# 2016_FDP_STRATEGIE.net
KiCad netlist of a schematic drawn in Altium Designer
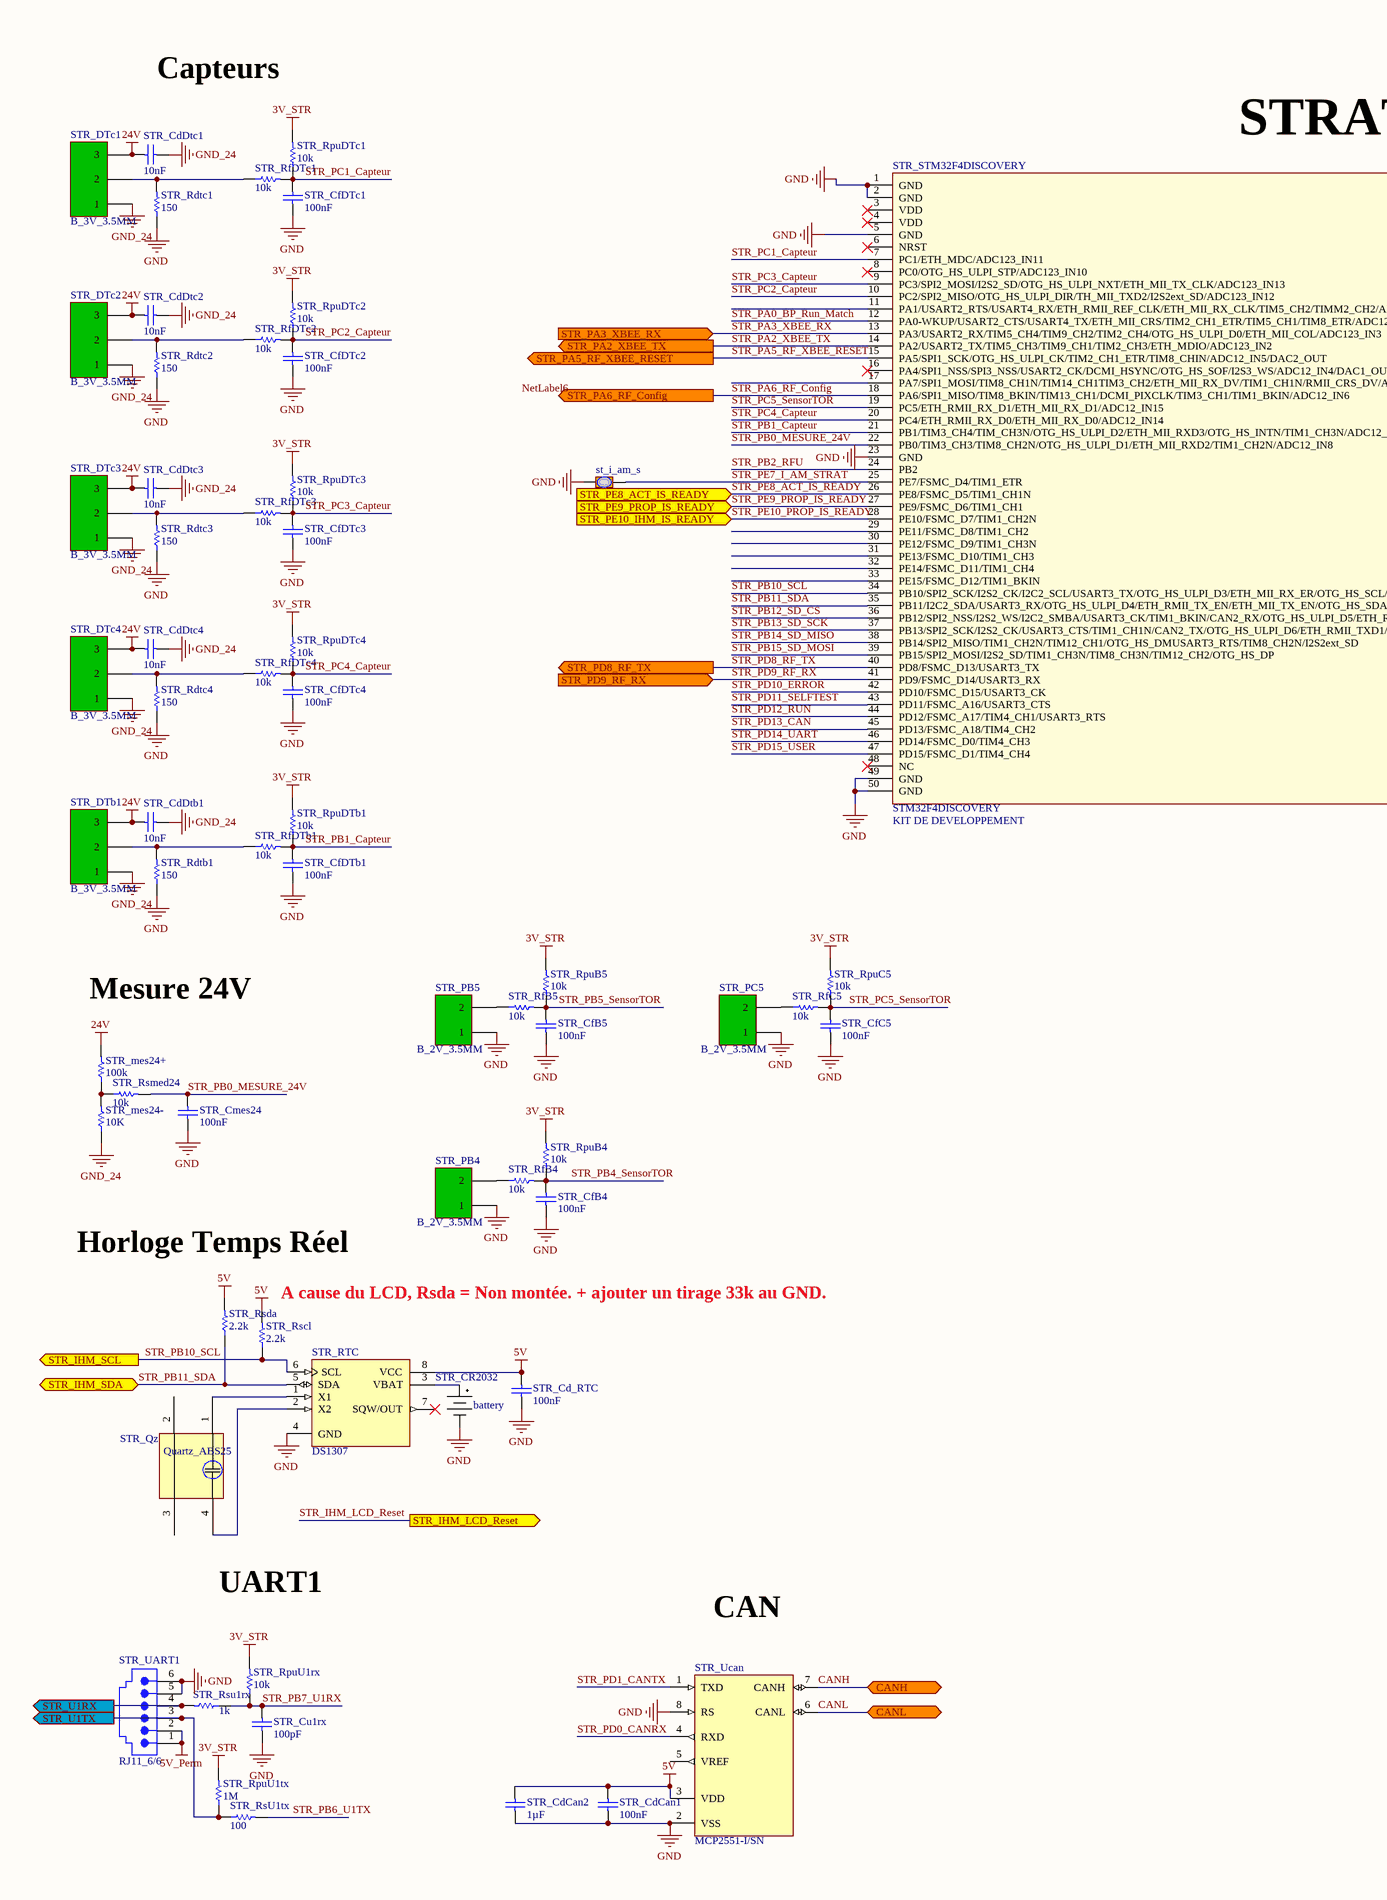
[diagram p0: 2016_FDP_STRATEGIE.SchDoc, left]
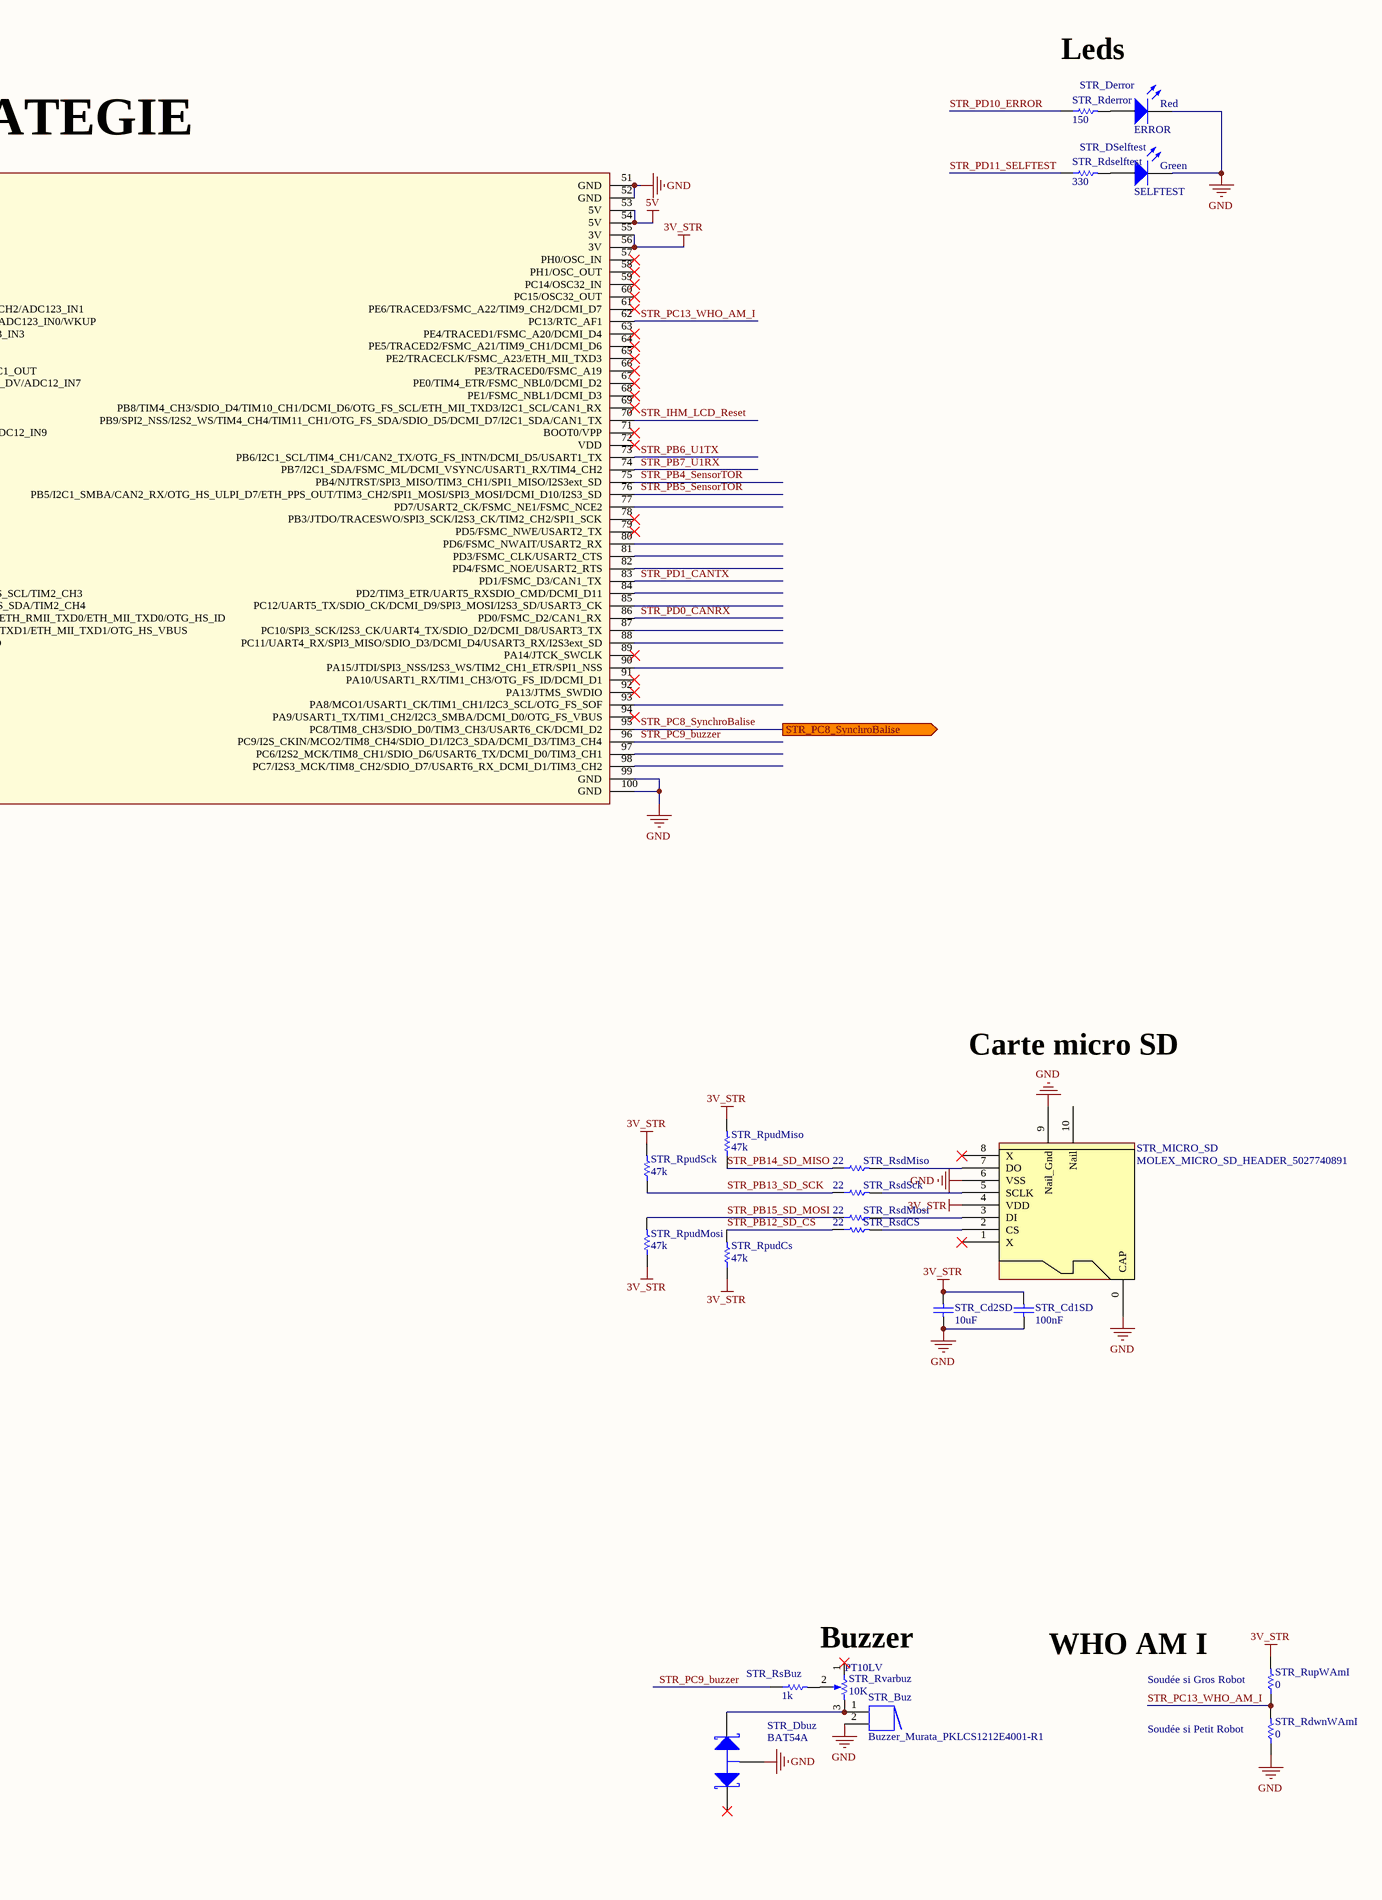
[diagram p1: 2016_FDP_STRATEGIE.SchDoc, right]

(export (version "E")
  (design (tool "Eeschema 10.0.6"))
  (components
    (comp (ref "STR_Buz")
      (value "Buzzer_Murata_PKLCS1212E4001-R1")
      (footprint "Buzzer_Murata PKLCS1212")
      (fields
        (field (name "MANUFACTURER") "MURATA")
        (field (name "MANUFACTURER PART NUMBER") "PKLCS1212E4001-R1")
      )
      (libsource (lib "DG_Buzzer") (part "Buzzer_Murata_PKLCS1212E4001-R1"))
    )
    (comp (ref "STR_Cd1SD")
      (value "100nF")
      (footprint "C0805_N")
      (description "Capacitor")
      (fields (field (name "PUBLISHER") "Altium Limited"))
      (libsource (lib "_ROBOT") (part "Condensateur"))
    )
    (comp (ref "STR_Cd2SD")
      (value "10uF")
      (footprint "C1206_N")
      (description "Capacitor")
      (fields (field (name "PUBLISHER") "Altium Limited"))
      (libsource (lib "_ROBOT") (part "Condensateur"))
    )
    (comp (ref "STR_CdCan1")
      (value "100nF")
      (footprint "C0805_N")
      (description "Capacitor")
      (fields (field (name "PUBLISHER") "Altium Limited"))
      (libsource (lib "_ROBOT") (part "Condensateur"))
    )
    (comp (ref "STR_CdCan2")
      (value "1µF")
      (footprint "C0805_N")
      (description "Capacitor")
      (fields (field (name "PUBLISHER") "Altium Limited"))
      (libsource (lib "_ROBOT") (part "Condensateur"))
    )
    (comp (ref "STR_CdDtb1")
      (value "10nF")
      (footprint "C0805_N")
      (description "Capacitor")
      (fields (field (name "PUBLISHER") "Altium Limited"))
      (libsource (lib "_ROBOT") (part "Condensateur"))
    )
    (comp (ref "STR_CdDtc1")
      (value "10nF")
      (footprint "C0805_N")
      (description "Capacitor")
      (fields (field (name "PUBLISHER") "Altium Limited"))
      (libsource (lib "_ROBOT") (part "Condensateur"))
    )
    (comp (ref "STR_CdDtc2")
      (value "10nF")
      (footprint "C0805_N")
      (description "Capacitor")
      (fields (field (name "PUBLISHER") "Altium Limited"))
      (libsource (lib "_ROBOT") (part "Condensateur"))
    )
    (comp (ref "STR_CdDtc3")
      (value "10nF")
      (footprint "C0805_N")
      (description "Capacitor")
      (fields (field (name "PUBLISHER") "Altium Limited"))
      (libsource (lib "_ROBOT") (part "Condensateur"))
    )
    (comp (ref "STR_CdDtc4")
      (value "10nF")
      (footprint "C0805_N")
      (description "Capacitor")
      (fields (field (name "PUBLISHER") "Altium Limited"))
      (libsource (lib "_ROBOT") (part "Condensateur"))
    )
    (comp (ref "STR_Cd_RTC")
      (value "100nF")
      (footprint "C0805_N")
      (description "Capacitor")
      (fields (field (name "PUBLISHER") "Altium Limited"))
      (libsource (lib "_ROBOT") (part "Condensateur"))
    )
    (comp (ref "STR_CfB4")
      (value "100nF")
      (footprint "C0805_N")
      (description "Capacitor")
      (fields (field (name "PUBLISHER") "Altium Limited"))
      (libsource (lib "_ROBOT") (part "Condensateur"))
    )
    (comp (ref "STR_CfB5")
      (value "100nF")
      (footprint "C0805_N")
      (description "Capacitor")
      (fields (field (name "PUBLISHER") "Altium Limited"))
      (libsource (lib "_ROBOT") (part "Condensateur"))
    )
    (comp (ref "STR_CfC5")
      (value "100nF")
      (footprint "C0805_N")
      (description "Capacitor")
      (fields (field (name "PUBLISHER") "Altium Limited"))
      (libsource (lib "_ROBOT") (part "Condensateur"))
    )
    (comp (ref "STR_CfDTb1")
      (value "100nF")
      (footprint "C0805_N")
      (description "Capacitor")
      (fields (field (name "PUBLISHER") "Altium Limited"))
      (libsource (lib "_ROBOT") (part "Condensateur"))
    )
    (comp (ref "STR_CfDTc1")
      (value "100nF")
      (footprint "C0805_N")
      (description "Capacitor")
      (fields (field (name "PUBLISHER") "Altium Limited"))
      (libsource (lib "_ROBOT") (part "Condensateur"))
    )
    (comp (ref "STR_CfDTc2")
      (value "100nF")
      (footprint "C0805_N")
      (description "Capacitor")
      (fields (field (name "PUBLISHER") "Altium Limited"))
      (libsource (lib "_ROBOT") (part "Condensateur"))
    )
    (comp (ref "STR_CfDTc3")
      (value "100nF")
      (footprint "C0805_N")
      (description "Capacitor")
      (fields (field (name "PUBLISHER") "Altium Limited"))
      (libsource (lib "_ROBOT") (part "Condensateur"))
    )
    (comp (ref "STR_CfDTc4")
      (value "100nF")
      (footprint "C0805_N")
      (description "Capacitor")
      (fields (field (name "PUBLISHER") "Altium Limited"))
      (libsource (lib "_ROBOT") (part "Condensateur"))
    )
    (comp (ref "STR_Cmes24")
      (value "100nF")
      (footprint "C0805_N")
      (description "Capacitor")
      (fields (field (name "PUBLISHER") "Altium Limited"))
      (libsource (lib "_ROBOT") (part "Condensateur"))
    )
    (comp (ref "STR_CR2032")
      (value "battery")
      (footprint "Pile_boutton")
      (description "Battery, Pile")
      (fields (field (name "PUBLISHER") "Jean-Philippe Oudet"))
      (libsource (lib "LibPocketTag") (part "battery"))
    )
    (comp (ref "STR_Cu1rx")
      (value "100pF")
      (footprint "C0805_N")
      (description "Capacitor")
      (fields (field (name "PUBLISHER") "Altium Limited"))
      (libsource (lib "_ROBOT") (part "Condensateur"))
    )
    (comp (ref "STR_Dbuz")
      (value "BAT54A")
      (footprint "SOT23-3N")
      (description "DIODE SCHOTTKY DOUBLE")
      (fields (field (name "MANUFACTURER") "ZETEX"))
      (libsource (lib "_ROBOT") (part "Diode Shottky double  BAT54A"))
    )
    (comp (ref "STR_Derror")
      (value "ERROR")
      (footprint "LED_0805")
      (description "Typical LED")
      (fields (field (name "PUBLISHER") "Altium Limited"))
      (libsource (lib "_ROBOT") (part "LED"))
    )
    (comp (ref "STR_DSelftest")
      (value "SELFTEST")
      (footprint "LED_0805")
      (description "Typical LED")
      (fields (field (name "PUBLISHER") "Altium Limited"))
      (libsource (lib "_ROBOT") (part "LED"))
    )
    (comp (ref "STR_DTb1")
      (value "B_3V_3.5MM")
      (footprint "BORNIER_3V_3.5MM")
      (libsource (lib "Connecteur") (part "BORNIER_3V_3.5MM"))
    )
    (comp (ref "STR_DTc1")
      (value "B_3V_3.5MM")
      (footprint "BORNIER_3V_3.5MM")
      (libsource (lib "Connecteur") (part "BORNIER_3V_3.5MM"))
    )
    (comp (ref "STR_DTc2")
      (value "B_3V_3.5MM")
      (footprint "BORNIER_3V_3.5MM")
      (libsource (lib "Connecteur") (part "BORNIER_3V_3.5MM"))
    )
    (comp (ref "STR_DTc3")
      (value "B_3V_3.5MM")
      (footprint "BORNIER_3V_3.5MM")
      (libsource (lib "Connecteur") (part "BORNIER_3V_3.5MM"))
    )
    (comp (ref "STR_DTc4")
      (value "B_3V_3.5MM")
      (footprint "BORNIER_3V_3.5MM")
      (libsource (lib "Connecteur") (part "BORNIER_3V_3.5MM"))
    )
    (comp (ref "STR_mes24+")
      (value "100k")
      (footprint "R1206_N")
      (description "Resistor")
      (fields (field (name "PUBLISHER") "Altium Limited"))
      (libsource (lib "_ROBOT") (part "Resistor"))
    )
    (comp (ref "STR_mes24-")
      (value "10K")
      (footprint "R1206_N")
      (description "Resistor")
      (fields (field (name "PUBLISHER") "Altium Limited"))
      (libsource (lib "_ROBOT") (part "Resistor"))
    )
    (comp (ref "STR_MICRO_SD")
      (value "MOLEX_MICRO_SD_HEADER_5027740891")
      (footprint "MOLEX_MICRO_SD_HEADER_5027740891")
      (libsource (lib "Connecteur") (part "MOLEX_MICRO_SD_HEADER_5027740891"))
    )
    (comp (ref "STR_PB4")
      (value "B_2V_3.5MM")
      (footprint "BORNIER_2V_3.5MM")
      (libsource (lib "Connecteur") (part "BORNIER_2V_3.5MM"))
    )
    (comp (ref "STR_PB5")
      (value "B_2V_3.5MM")
      (footprint "BORNIER_2V_3.5MM")
      (libsource (lib "Connecteur") (part "BORNIER_2V_3.5MM"))
    )
    (comp (ref "STR_PC5")
      (value "B_2V_3.5MM")
      (footprint "BORNIER_2V_3.5MM")
      (libsource (lib "Connecteur") (part "BORNIER_2V_3.5MM"))
    )
    (comp (ref "STR_Qz")
      (value "Quartz_ABS25")
      (footprint "Quartz_ABS25")
      (libsource (lib "_ROBOT") (part "Quartz_ABS25"))
    )
    (comp (ref "STR_Rderror")
      (value "150")
      (footprint "R1206_N")
      (description "Resistor")
      (fields (field (name "PUBLISHER") "Altium Limited"))
      (libsource (lib "_ROBOT") (part "Resistor"))
    )
    (comp (ref "STR_Rdselftest")
      (value "330")
      (footprint "R1206_N")
      (description "Resistor")
      (fields (field (name "PUBLISHER") "Altium Limited"))
      (libsource (lib "_ROBOT") (part "Resistor"))
    )
    (comp (ref "STR_Rdtb1")
      (value "150")
      (footprint "R1206_N")
      (description "Resistor")
      (fields (field (name "PUBLISHER") "Altium Limited"))
      (libsource (lib "_ROBOT") (part "Resistor"))
    )
    (comp (ref "STR_Rdtc1")
      (value "150")
      (footprint "R1206_N")
      (description "Resistor")
      (fields (field (name "PUBLISHER") "Altium Limited"))
      (libsource (lib "_ROBOT") (part "Resistor"))
    )
    (comp (ref "STR_Rdtc2")
      (value "150")
      (footprint "R1206_N")
      (description "Resistor")
      (fields (field (name "PUBLISHER") "Altium Limited"))
      (libsource (lib "_ROBOT") (part "Resistor"))
    )
    (comp (ref "STR_Rdtc3")
      (value "150")
      (footprint "R1206_N")
      (description "Resistor")
      (fields (field (name "PUBLISHER") "Altium Limited"))
      (libsource (lib "_ROBOT") (part "Resistor"))
    )
    (comp (ref "STR_Rdtc4")
      (value "150")
      (footprint "R1206_N")
      (description "Resistor")
      (fields (field (name "PUBLISHER") "Altium Limited"))
      (libsource (lib "_ROBOT") (part "Resistor"))
    )
    (comp (ref "STR_RdwnWAmI")
      (value "0")
      (footprint "R1206_N")
      (description "Resistor")
      (fields (field (name "PUBLISHER") "Altium Limited"))
      (libsource (lib "_ROBOT") (part "Resistor"))
    )
    (comp (ref "STR_RfB4")
      (value "10k")
      (footprint "R1206_N")
      (description "Resistor")
      (fields (field (name "PUBLISHER") "Altium Limited"))
      (libsource (lib "_ROBOT") (part "Resistor"))
    )
    (comp (ref "STR_RfB5")
      (value "10k")
      (footprint "R1206_N")
      (description "Resistor")
      (fields (field (name "PUBLISHER") "Altium Limited"))
      (libsource (lib "_ROBOT") (part "Resistor"))
    )
    (comp (ref "STR_RfC5")
      (value "10k")
      (footprint "R1206_N")
      (description "Resistor")
      (fields (field (name "PUBLISHER") "Altium Limited"))
      (libsource (lib "_ROBOT") (part "Resistor"))
    )
    (comp (ref "STR_RfDTb1")
      (value "10k")
      (footprint "R1206_N")
      (description "Resistor")
      (fields (field (name "PUBLISHER") "Altium Limited"))
      (libsource (lib "_ROBOT") (part "Resistor"))
    )
    (comp (ref "STR_RfDTc1")
      (value "10k")
      (footprint "R1206_N")
      (description "Resistor")
      (fields (field (name "PUBLISHER") "Altium Limited"))
      (libsource (lib "_ROBOT") (part "Resistor"))
    )
    (comp (ref "STR_RfDTc2")
      (value "10k")
      (footprint "R1206_N")
      (description "Resistor")
      (fields (field (name "PUBLISHER") "Altium Limited"))
      (libsource (lib "_ROBOT") (part "Resistor"))
    )
    (comp (ref "STR_RfDTc3")
      (value "10k")
      (footprint "R1206_N")
      (description "Resistor")
      (fields (field (name "PUBLISHER") "Altium Limited"))
      (libsource (lib "_ROBOT") (part "Resistor"))
    )
    (comp (ref "STR_RfDTc4")
      (value "10k")
      (footprint "R1206_N")
      (description "Resistor")
      (fields (field (name "PUBLISHER") "Altium Limited"))
      (libsource (lib "_ROBOT") (part "Resistor"))
    )
    (comp (ref "STR_RpuB4")
      (value "10k")
      (footprint "R1206_N")
      (description "Resistor")
      (fields (field (name "PUBLISHER") "Altium Limited"))
      (libsource (lib "_ROBOT") (part "Resistor"))
    )
    (comp (ref "STR_RpuB5")
      (value "10k")
      (footprint "R1206_N")
      (description "Resistor")
      (fields (field (name "PUBLISHER") "Altium Limited"))
      (libsource (lib "_ROBOT") (part "Resistor"))
    )
    (comp (ref "STR_RpuC5")
      (value "10k")
      (footprint "R1206_N")
      (description "Resistor")
      (fields (field (name "PUBLISHER") "Altium Limited"))
      (libsource (lib "_ROBOT") (part "Resistor"))
    )
    (comp (ref "STR_RpudCs")
      (value "47k")
      (footprint "R1206_N")
      (description "Resistor")
      (fields (field (name "PUBLISHER") "Altium Limited"))
      (libsource (lib "_ROBOT") (part "Resistor"))
    )
    (comp (ref "STR_RpudMiso")
      (value "47k")
      (footprint "R1206_N")
      (description "Resistor")
      (fields (field (name "PUBLISHER") "Altium Limited"))
      (libsource (lib "_ROBOT") (part "Resistor"))
    )
    (comp (ref "STR_RpudMosi")
      (value "47k")
      (footprint "R1206_N")
      (description "Resistor")
      (fields (field (name "PUBLISHER") "Altium Limited"))
      (libsource (lib "_ROBOT") (part "Resistor"))
    )
    (comp (ref "STR_RpudSck")
      (value "47k")
      (footprint "R1206_N")
      (description "Resistor")
      (fields (field (name "PUBLISHER") "Altium Limited"))
      (libsource (lib "_ROBOT") (part "Resistor"))
    )
    (comp (ref "STR_RpuDTb1")
      (value "10k")
      (footprint "R1206_N")
      (description "Resistor")
      (fields (field (name "PUBLISHER") "Altium Limited"))
      (libsource (lib "_ROBOT") (part "Resistor"))
    )
    (comp (ref "STR_RpuDTc1")
      (value "10k")
      (footprint "R1206_N")
      (description "Resistor")
      (fields (field (name "PUBLISHER") "Altium Limited"))
      (libsource (lib "_ROBOT") (part "Resistor"))
    )
    (comp (ref "STR_RpuDTc2")
      (value "10k")
      (footprint "R1206_N")
      (description "Resistor")
      (fields (field (name "PUBLISHER") "Altium Limited"))
      (libsource (lib "_ROBOT") (part "Resistor"))
    )
    (comp (ref "STR_RpuDTc3")
      (value "10k")
      (footprint "R1206_N")
      (description "Resistor")
      (fields (field (name "PUBLISHER") "Altium Limited"))
      (libsource (lib "_ROBOT") (part "Resistor"))
    )
    (comp (ref "STR_RpuDTc4")
      (value "10k")
      (footprint "R1206_N")
      (description "Resistor")
      (fields (field (name "PUBLISHER") "Altium Limited"))
      (libsource (lib "_ROBOT") (part "Resistor"))
    )
    (comp (ref "STR_RpuU1rx")
      (value "10k")
      (footprint "R1206_N")
      (description "Resistor")
      (fields (field (name "PUBLISHER") "Altium Limited"))
      (libsource (lib "_ROBOT") (part "Resistor"))
    )
    (comp (ref "STR_RpuU1tx")
      (value "1M")
      (footprint "R1206_N")
      (description "Resistor")
      (fields (field (name "PUBLISHER") "Altium Limited"))
      (libsource (lib "_ROBOT") (part "Resistor"))
    )
    (comp (ref "STR_RsBuz")
      (value "1k")
      (footprint "R1206_N")
      (description "Resistor")
      (fields (field (name "PUBLISHER") "Altium Limited"))
      (libsource (lib "_ROBOT") (part "Resistor"))
    )
    (comp (ref "STR_Rscl")
      (value "2.2k")
      (footprint "R1206_N")
      (description "Resistor")
      (fields (field (name "PUBLISHER") "Altium Limited"))
      (libsource (lib "_ROBOT") (part "Resistor"))
    )
    (comp (ref "STR_Rsda")
      (value "2.2k")
      (footprint "R1206_N")
      (description "Resistor")
      (fields (field (name "PUBLISHER") "Altium Limited"))
      (libsource (lib "_ROBOT") (part "Resistor"))
    )
    (comp (ref "STR_RsdCS")
      (value "22")
      (footprint "R1206_N")
      (description "Resistor")
      (fields (field (name "PUBLISHER") "Altium Limited"))
      (libsource (lib "_ROBOT") (part "Resistor"))
    )
    (comp (ref "STR_RsdMiso")
      (value "22")
      (footprint "R1206_N")
      (description "Resistor")
      (fields (field (name "PUBLISHER") "Altium Limited"))
      (libsource (lib "_ROBOT") (part "Resistor"))
    )
    (comp (ref "STR_RsdMosi")
      (value "22")
      (footprint "R1206_N")
      (description "Resistor")
      (fields (field (name "PUBLISHER") "Altium Limited"))
      (libsource (lib "_ROBOT") (part "Resistor"))
    )
    (comp (ref "STR_RsdSck")
      (value "22")
      (footprint "R1206_N")
      (description "Resistor")
      (fields (field (name "PUBLISHER") "Altium Limited"))
      (libsource (lib "_ROBOT") (part "Resistor"))
    )
    (comp (ref "STR_Rsmed24")
      (value "10k")
      (footprint "R1206_N")
      (description "Resistor")
      (fields (field (name "PUBLISHER") "Altium Limited"))
      (libsource (lib "_ROBOT") (part "Resistor"))
    )
    (comp (ref "STR_Rsu1rx")
      (value "1k")
      (footprint "R1206_N")
      (description "Resistor")
      (fields (field (name "PUBLISHER") "Altium Limited"))
      (libsource (lib "_ROBOT") (part "Resistor"))
    )
    (comp (ref "STR_RsU1tx")
      (value "100")
      (footprint "R1206_N")
      (description "Resistor")
      (fields (field (name "PUBLISHER") "Altium Limited"))
      (libsource (lib "_ROBOT") (part "Resistor"))
    )
    (comp (ref "STR_RTC")
      (value "DS1307")
      (footprint "SO8_N")
      (description "64 X 8 Serial Real-Time Clock")
      (fields (field (name "PUBLISHER") "Altium Limited"))
      (libsource (lib "Robot2010") (part "DS1307"))
    )
    (comp (ref "STR_RupWAmI")
      (value "0")
      (footprint "R1206_N")
      (description "Resistor")
      (fields (field (name "PUBLISHER") "Altium Limited"))
      (libsource (lib "_ROBOT") (part "Resistor"))
    )
    (comp (ref "STR_Rvarbuz")
      (value "10K")
      (footprint "TRIMMER_MONOTOUR_PT10LV")
      (description "RESISTANCE VARIABLE_TRAVERSANTE : PT10LV")
      (fields
        (field (name "TYPE") "PT10LV")
        (field (name "Comment") "RESISTANCE_VARIABLE_TRAVERSANTE : PT10LV")
      )
      (libsource (lib "composants passifs") (part "RESISTANCE_VARIABLE_TRAVERSANTE {colon} PT10LV"))
    )
    (comp (ref "STR_STM32F4DISCOVERY")
      (value "STM32F4DISCOVERY")
      (footprint "STM32_F4DISCOVERY")
      (description "KIT DE DEVELOPPEMENT POUR MICROCONTROLEUR STM32F407VGT6")
      (fields (field (name "TYPE") "KIT DE DEVELOPPEMENT"))
      (libsource (lib "circuits integres") (part "STM32F4DISCOVERY"))
    )
    (comp (ref "STR_UART1")
      (value "RJ11_6/6")
      (footprint "RJ11_6/6 - droit")
      (description "Right Angle, Standard Profile, Offset Latch DECconnect, Flangeless PCB Jack")
      (fields (field (name "PUBLISHER") "Altium Limited"))
      (libsource (lib "Connecteur") (part "RJ11_6/6"))
    )
    (comp (ref "STR_Ucan")
      (value "MCP2551-I/SN")
      (footprint "SO8_N")
      (description "High-Speed CAN Transceiver, 8-Pin SOIC, Industrial Temperature")
      (fields (field (name "PUBLISHER") "Damien Guitton"))
      (libsource (lib "Circuit intégré") (part "MCP2551-I/SN"))
    )
    (comp (ref "st_i_am_s")
      (value "Goutte Strap_2")
      (footprint "Goutte Strap_2 Pads_Clearance 0.254mm")
      (fields (field (name "PUBLISHER") "Damien Guitton"))
      (libsource (lib "DG_Connecteur") (part "Goutte Strap_2"))
    )
  )
  (nets
    (net (code "1") (name "/CANH") (class "Default")
      (node (ref "STR_Ucan") (pin "7") (pinfunction "CANH_7") (pintype "bidirectional"))
    )
    (net (code "2") (name "/CANL") (class "Default")
      (node (ref "STR_Ucan") (pin "6") (pinfunction "CANL_6") (pintype "bidirectional"))
    )
    (net (code "4") (name "/STR_IHM_LCD_Reset") (class "Default")
      (node (ref "STR_STM32F4DISCOVERY") (pin "70") (pinfunction "PB9/SPI2_NSS/I2S2_WS/TIM4_CH4/TIM11_CH1/OTG_FS_SDA/SDIO_D5/DCMI_D7/I2C1_SDA/CAN1_TX_70") (pintype "passive"))
    )
    (net (code "5") (name "/STR_PA0_BP_Run_Match") (class "Default")
      (node (ref "STR_STM32F4DISCOVERY") (pin "12") (pinfunction "PA0-WKUP/USART2_CTS/USART4_TX/ETH_MII_CRS/TIM2_CH1_ETR/TIM5_CH1/TIM8_ETR/ADC123_IN0/WKUP_12") (pintype "passive"))
    )
    (net (code "6") (name "/STR_PA2_XBEE_TX") (class "Default")
      (node (ref "STR_STM32F4DISCOVERY") (pin "14") (pinfunction "PA2/USART2_TX/TIM5_CH3/TIM9_CH1/TIM2_CH3/ETH_MDIO/ADC123_IN2_14") (pintype "passive"))
    )
    (net (code "7") (name "/STR_PA3_XBEE_RX") (class "Default")
      (node (ref "STR_STM32F4DISCOVERY") (pin "13") (pinfunction "PA3/USART2_RX/TIM5_CH4/TIM9_CH2/TIM2_CH4/OTG_HS_ULPI_D0/ETH_MII_COL/ADC123_IN3_13") (pintype "passive"))
    )
    (net (code "8") (name "/STR_PA5_RF_XBEE_RESET") (class "Default")
      (node (ref "STR_STM32F4DISCOVERY") (pin "15") (pinfunction "PA5/SPI1_SCK/OTG_HS_ULPI_CK/TIM2_CH1_ETR/TIM8_CHIN/ADC12_IN5/DAC2_OUT_15") (pintype "passive"))
    )
    (net (code "9") (name "/STR_PA6_RF_Config") (class "Default")
      (node (ref "STR_STM32F4DISCOVERY") (pin "18") (pinfunction "PA6/SPI1_MISO/TIM8_BKIN/TIM13_CH1/DCMI_PIXCLK/TIM3_CH1/TIM1_BKIN/ADC12_IN6_18") (pintype "passive"))
    )
    (net (code "10") (name "/STR_PB0_MESURE_24V") (class "Default")
      (node (ref "STR_Cmes24") (pin "2") (pinfunction "2_2") (pintype "passive"))
      (node (ref "STR_Rsmed24") (pin "2") (pinfunction "2_2") (pintype "passive"))
      (node (ref "STR_STM32F4DISCOVERY") (pin "22") (pinfunction "PB0/TIM3_CH3/TIM8_CH2N/OTG_HS_ULPI_D1/ETH_MII_RXD2/TIM1_CH2N/ADC12_IN8_22") (pintype "passive"))
    )
    (net (code "11") (name "/STR_PB1_Capteur") (class "Default")
      (node (ref "STR_CfDTb1") (pin "2") (pinfunction "2_2") (pintype "passive"))
      (node (ref "STR_RfDTb1") (pin "2") (pinfunction "2_2") (pintype "passive"))
      (node (ref "STR_RpuDTb1") (pin "1") (pinfunction "1_1") (pintype "passive"))
      (node (ref "STR_STM32F4DISCOVERY") (pin "21") (pinfunction "PB1/TIM3_CH4/TIM_CH3N/OTG_HS_ULPI_D2/ETH_MII_RXD3/OTG_HS_INTN/TIM1_CH3N/ADC12_IN9_21") (pintype "passive"))
    )
    (net (code "12") (name "/STR_PB2_RFU") (class "Default")
      (node (ref "STR_STM32F4DISCOVERY") (pin "24") (pinfunction "PB2_24") (pintype "passive"))
    )
    (net (code "13") (name "/STR_PB4_SensorTOR") (class "Default")
      (node (ref "STR_CfB4") (pin "2") (pinfunction "2_2") (pintype "passive"))
      (node (ref "STR_RfB4") (pin "2") (pinfunction "2_2") (pintype "passive"))
      (node (ref "STR_RpuB4") (pin "1") (pinfunction "1_1") (pintype "passive"))
      (node (ref "STR_STM32F4DISCOVERY") (pin "75") (pinfunction "PB4/NJTRST/SPI3_MISO/TIM3_CH1/SPI1_MISO/I2S3ext_SD_75") (pintype "passive"))
    )
    (net (code "14") (name "/STR_PB5_SensorTOR") (class "Default")
      (node (ref "STR_CfB5") (pin "2") (pinfunction "2_2") (pintype "passive"))
      (node (ref "STR_RfB5") (pin "2") (pinfunction "2_2") (pintype "passive"))
      (node (ref "STR_RpuB5") (pin "1") (pinfunction "1_1") (pintype "passive"))
      (node (ref "STR_STM32F4DISCOVERY") (pin "76") (pinfunction "PB5/I2C1_SMBA/CAN2_RX/OTG_HS_ULPI_D7/ETH_PPS_OUT/TIM3_CH2/SPI1_MOSI/SPI3_MOSI/DCMI_D10/I2S3_SD_76") (pintype "passive"))
    )
    (net (code "15") (name "/STR_PB6_U1TX") (class "Default")
      (node (ref "STR_RsU1tx") (pin "2") (pinfunction "2_2") (pintype "passive"))
      (node (ref "STR_STM32F4DISCOVERY") (pin "73") (pinfunction "PB6/I2C1_SCL/TIM4_CH1/CAN2_TX/OTG_FS_INTN/DCMI_D5/USART1_TX_73") (pintype "passive"))
    )
    (net (code "16") (name "/STR_PB7_U1RX") (class "Default")
      (node (ref "STR_Cu1rx") (pin "2") (pinfunction "2_2") (pintype "passive"))
      (node (ref "STR_RpuU1rx") (pin "1") (pinfunction "1_1") (pintype "passive"))
      (node (ref "STR_Rsu1rx") (pin "1") (pinfunction "1_1") (pintype "passive"))
      (node (ref "STR_STM32F4DISCOVERY") (pin "74") (pinfunction "PB7/I2C1_SDA/FSMC_ML/DCMI_VSYNC/USART1_RX/TIM4_CH2_74") (pintype "passive"))
    )
    (net (code "17") (name "/STR_PB10_SCL") (class "Default")
      (node (ref "STR_RTC") (pin "6") (pinfunction "SCL_6") (pintype "input"))
      (node (ref "STR_Rscl") (pin "1") (pinfunction "1_1") (pintype "passive"))
      (node (ref "STR_STM32F4DISCOVERY") (pin "34") (pinfunction "PB10/SPI2_SCK/I2S2_CK/I2C2_SCL/USART3_TX/OTG_HS_ULPI_D3/ETH_MII_RX_ER/OTG_HS_SCL/TIM2_CH3_34") (pintype "passive"))
    )
    (net (code "18") (name "/STR_PB11_SDA") (class "Default")
      (node (ref "STR_RTC") (pin "5") (pinfunction "SDA_5") (pintype "bidirectional"))
      (node (ref "STR_Rsda") (pin "1") (pinfunction "1_1") (pintype "passive"))
      (node (ref "STR_STM32F4DISCOVERY") (pin "35") (pinfunction "PB11/I2C2_SDA/USART3_RX/OTG_HS_ULPI_D4/ETH_RMII_TX_EN/ETH_MII_TX_EN/OTG_HS_SDA/TIM2_CH4_35") (pintype "passive"))
    )
    (net (code "19") (name "/STR_PB12_SD_CS") (class "Default")
      (node (ref "STR_RpudCs") (pin "2") (pinfunction "2_2") (pintype "passive"))
      (node (ref "STR_RsdCS") (pin "1") (pinfunction "1_1") (pintype "passive"))
      (node (ref "STR_STM32F4DISCOVERY") (pin "36") (pinfunction "PB12/SPI2_NSS/I2S2_WS/I2C2_SMBA/USART3_CK/TIM1_BKIN/CAN2_RX/OTG_HS_ULPI_D5/ETH_RMII_TXD0/ETH_MII_TXD0/OTG_HS_ID_36") (pintype "passive"))
    )
    (net (code "20") (name "/STR_PB13_SD_SCK") (class "Default")
      (node (ref "STR_RpudSck") (pin "1") (pinfunction "1_1") (pintype "passive"))
      (node (ref "STR_RsdSck") (pin "1") (pinfunction "1_1") (pintype "passive"))
      (node (ref "STR_STM32F4DISCOVERY") (pin "37") (pinfunction "PB13/SPI2_SCK/I2S2_CK/USART3_CTS/TIM1_CH1N/CAN2_TX/OTG_HS_ULPI_D6/ETH_RMII_TXD1/ETH_MII_TXD1/OTG_HS_VBUS_37") (pintype "passive"))
    )
    (net (code "21") (name "/STR_PB14_SD_MISO") (class "Default")
      (node (ref "STR_RpudMiso") (pin "1") (pinfunction "1_1") (pintype "passive"))
      (node (ref "STR_RsdMiso") (pin "1") (pinfunction "1_1") (pintype "passive"))
      (node (ref "STR_STM32F4DISCOVERY") (pin "38") (pinfunction "PB14/SPI2_MISO/TIM1_CH2N/TIM12_CH1/OTG_HS_DMUSART3_RTS/TIM8_CH2N/I2S2ext_SD_38") (pintype "passive"))
    )
    (net (code "22") (name "/STR_PB15_SD_MOSI") (class "Default")
      (node (ref "STR_RpudMosi") (pin "2") (pinfunction "2_2") (pintype "passive"))
      (node (ref "STR_RsdMosi") (pin "1") (pinfunction "1_1") (pintype "passive"))
      (node (ref "STR_STM32F4DISCOVERY") (pin "39") (pinfunction "PB15/SPI2_MOSI/I2S2_SD/TIM1_CH3N/TIM8_CH3N/TIM12_CH2/OTG_HS_DP_39") (pintype "passive"))
    )
    (net (code "23") (name "/STR_PC1_Capteur") (class "Default")
      (node (ref "STR_CfDTc1") (pin "2") (pinfunction "2_2") (pintype "passive"))
      (node (ref "STR_RfDTc1") (pin "2") (pinfunction "2_2") (pintype "passive"))
      (node (ref "STR_RpuDTc1") (pin "1") (pinfunction "1_1") (pintype "passive"))
      (node (ref "STR_STM32F4DISCOVERY") (pin "7") (pinfunction "PC1/ETH_MDC/ADC123_IN11_7") (pintype "passive"))
    )
    (net (code "24") (name "/STR_PC2_Capteur") (class "Default")
      (node (ref "STR_CfDTc2") (pin "2") (pinfunction "2_2") (pintype "passive"))
      (node (ref "STR_RfDTc2") (pin "2") (pinfunction "2_2") (pintype "passive"))
      (node (ref "STR_RpuDTc2") (pin "1") (pinfunction "1_1") (pintype "passive"))
      (node (ref "STR_STM32F4DISCOVERY") (pin "10") (pinfunction "PC2/SPI2_MISO/OTG_HS_ULPI_DIR/TH_MII_TXD2/I2S2ext_SD/ADC123_IN12_10") (pintype "passive"))
    )
    (net (code "25") (name "/STR_PC3_Capteur") (class "Default")
      (node (ref "STR_CfDTc3") (pin "2") (pinfunction "2_2") (pintype "passive"))
      (node (ref "STR_RfDTc3") (pin "2") (pinfunction "2_2") (pintype "passive"))
      (node (ref "STR_RpuDTc3") (pin "1") (pinfunction "1_1") (pintype "passive"))
      (node (ref "STR_STM32F4DISCOVERY") (pin "9") (pinfunction "PC3/SPI2_MOSI/I2S2_SD/OTG_HS_ULPI_NXT/ETH_MII_TX_CLK/ADC123_IN13_9") (pintype "passive"))
    )
    (net (code "26") (name "/STR_PC4_Capteur") (class "Default")
      (node (ref "STR_CfDTc4") (pin "2") (pinfunction "2_2") (pintype "passive"))
      (node (ref "STR_RfDTc4") (pin "2") (pinfunction "2_2") (pintype "passive"))
      (node (ref "STR_RpuDTc4") (pin "1") (pinfunction "1_1") (pintype "passive"))
      (node (ref "STR_STM32F4DISCOVERY") (pin "20") (pinfunction "PC4/ETH_RMII_RX_D0/ETH_MII_RX_D0/ADC12_IN14_20") (pintype "passive"))
    )
    (net (code "27") (name "/STR_PC5_SensorTOR") (class "Default")
      (node (ref "STR_CfC5") (pin "2") (pinfunction "2_2") (pintype "passive"))
      (node (ref "STR_RfC5") (pin "2") (pinfunction "2_2") (pintype "passive"))
      (node (ref "STR_RpuC5") (pin "1") (pinfunction "1_1") (pintype "passive"))
      (node (ref "STR_STM32F4DISCOVERY") (pin "19") (pinfunction "PC5/ETH_RMII_RX_D1/ETH_MII_RX_D1/ADC12_IN15_19") (pintype "passive"))
    )
    (net (code "28") (name "/STR_PC8_SynchroBalise") (class "Default")
      (node (ref "STR_STM32F4DISCOVERY") (pin "95") (pinfunction "PC8/TIM8_CH3/SDIO_D0/TIM3_CH3/USART6_CK/DCMI_D2_95") (pintype "passive"))
    )
    (net (code "29") (name "/STR_PC9_buzzer") (class "Default")
      (node (ref "STR_RsBuz") (pin "1") (pinfunction "1_1") (pintype "passive"))
      (node (ref "STR_STM32F4DISCOVERY") (pin "96") (pinfunction "PC9/I2S_CKIN/MCO2/TIM8_CH4/SDIO_D1/I2C3_SDA/DCMI_D3/TIM3_CH4_96") (pintype "passive"))
    )
    (net (code "30") (name "/STR_PC13_WHO_AM_I") (class "Default")
      (node (ref "STR_RdwnWAmI") (pin "2") (pinfunction "2_2") (pintype "passive"))
      (node (ref "STR_RupWAmI") (pin "1") (pinfunction "1_1") (pintype "passive"))
      (node (ref "STR_STM32F4DISCOVERY") (pin "62") (pinfunction "PC13/RTC_AF1_62") (pintype "passive"))
    )
    (net (code "31") (name "/STR_PD0_CANRX") (class "Default")
      (node (ref "STR_STM32F4DISCOVERY") (pin "86") (pinfunction "PD0/FSMC_D2/CAN1_RX_86") (pintype "passive"))
      (node (ref "STR_Ucan") (pin "4") (pinfunction "RXD_4") (pintype "output"))
    )
    (net (code "32") (name "/STR_PD1_CANTX") (class "Default")
      (node (ref "STR_STM32F4DISCOVERY") (pin "83") (pinfunction "PD1/FSMC_D3/CAN1_TX_83") (pintype "passive"))
      (node (ref "STR_Ucan") (pin "1") (pinfunction "TXD_1") (pintype "input"))
    )
    (net (code "33") (name "/STR_PD8_RF_TX") (class "Default")
      (node (ref "STR_STM32F4DISCOVERY") (pin "40") (pinfunction "PD8/FSMC_D13/USART3_TX_40") (pintype "passive"))
    )
    (net (code "34") (name "/STR_PD9_RF_RX") (class "Default")
      (node (ref "STR_STM32F4DISCOVERY") (pin "41") (pinfunction "PD9/FSMC_D14/USART3_RX_41") (pintype "passive"))
    )
    (net (code "35") (name "/STR_PD10_ERROR") (class "Default")
      (node (ref "STR_Rderror") (pin "1") (pinfunction "1_1") (pintype "passive"))
      (node (ref "STR_STM32F4DISCOVERY") (pin "42") (pinfunction "PD10/FSMC_D15/USART3_CK_42") (pintype "passive"))
    )
    (net (code "36") (name "/STR_PD11_SELFTEST") (class "Default")
      (node (ref "STR_Rdselftest") (pin "1") (pinfunction "1_1") (pintype "passive"))
      (node (ref "STR_STM32F4DISCOVERY") (pin "43") (pinfunction "PD11/FSMC_A16/USART3_CTS_43") (pintype "passive"))
    )
    (net (code "37") (name "/STR_PD12_RUN") (class "Default")
      (node (ref "STR_STM32F4DISCOVERY") (pin "44") (pinfunction "PD12/FSMC_A17/TIM4_CH1/USART3_RTS_44") (pintype "passive"))
    )
    (net (code "38") (name "/STR_PD13_CAN") (class "Default")
      (node (ref "STR_STM32F4DISCOVERY") (pin "45") (pinfunction "PD13/FSMC_A18/TIM4_CH2_45") (pintype "passive"))
    )
    (net (code "39") (name "/STR_PD14_UART") (class "Default")
      (node (ref "STR_STM32F4DISCOVERY") (pin "46") (pinfunction "PD14/FSMC_D0/TIM4_CH3_46") (pintype "passive"))
    )
    (net (code "40") (name "/STR_PD15_USER") (class "Default")
      (node (ref "STR_STM32F4DISCOVERY") (pin "47") (pinfunction "PD15/FSMC_D1/TIM4_CH4_47") (pintype "passive"))
    )
    (net (code "41") (name "/STR_PE7_I_AM_STRAT") (class "Default")
      (node (ref "STR_STM32F4DISCOVERY") (pin "25") (pinfunction "PE7/FSMC_D4/TIM1_ETR_25") (pintype "passive"))
      (node (ref "st_i_am_s") (pin "2") (pinfunction "2_2") (pintype "passive"))
    )
    (net (code "42") (name "/STR_PE8_ACT_IS_READY") (class "Default")
      (node (ref "STR_STM32F4DISCOVERY") (pin "26") (pinfunction "PE8/FSMC_D5/TIM1_CH1N_26") (pintype "passive"))
    )
    (net (code "43") (name "/STR_PE9_PROP_IS_READY") (class "Default")
      (node (ref "STR_STM32F4DISCOVERY") (pin "27") (pinfunction "PE9/FSMC_D6/TIM1_CH1_27") (pintype "passive"))
    )
    (net (code "44") (name "/STR_PE10_PROP_IS_READY") (class "Default")
      (node (ref "STR_STM32F4DISCOVERY") (pin "28") (pinfunction "PE10/FSMC_D7/TIM1_CH2N_28") (pintype "passive"))
    )
    (net (code "45") (name "/STR_U1RX") (class "Default")
      (node (ref "STR_Rsu1rx") (pin "2") (pinfunction "2_2") (pintype "passive"))
      (node (ref "STR_UART1") (pin "4") (pinfunction "4_4") (pintype "passive"))
    )
    (net (code "46") (name "/STR_U1TX") (class "Default")
      (node (ref "STR_RpuU1tx") (pin "1") (pinfunction "1_1") (pintype "passive"))
      (node (ref "STR_RsU1tx") (pin "1") (pinfunction "1_1") (pintype "passive"))
      (node (ref "STR_UART1") (pin "3") (pinfunction "3_3") (pintype "passive"))
    )
    (net (code "47") (name "3V_STR") (class "Default")
      (node (ref "STR_Cd1SD") (pin "2") (pinfunction "2_2") (pintype "passive"))
      (node (ref "STR_Cd2SD") (pin "2") (pinfunction "2_2") (pintype "passive"))
      (node (ref "STR_MICRO_SD") (pin "4") (pinfunction "VDD_4") (pintype "passive"))
      (node (ref "STR_RpuB4") (pin "2") (pinfunction "2_2") (pintype "passive"))
      (node (ref "STR_RpuB5") (pin "2") (pinfunction "2_2") (pintype "passive"))
      (node (ref "STR_RpuC5") (pin "2") (pinfunction "2_2") (pintype "passive"))
      (node (ref "STR_RpuDTb1") (pin "2") (pinfunction "2_2") (pintype "passive"))
      (node (ref "STR_RpuDTc1") (pin "2") (pinfunction "2_2") (pintype "passive"))
      (node (ref "STR_RpuDTc2") (pin "2") (pinfunction "2_2") (pintype "passive"))
      (node (ref "STR_RpuDTc3") (pin "2") (pinfunction "2_2") (pintype "passive"))
      (node (ref "STR_RpuDTc4") (pin "2") (pinfunction "2_2") (pintype "passive"))
      (node (ref "STR_RpuU1rx") (pin "2") (pinfunction "2_2") (pintype "passive"))
      (node (ref "STR_RpuU1tx") (pin "2") (pinfunction "2_2") (pintype "passive"))
      (node (ref "STR_RpudCs") (pin "1") (pinfunction "1_1") (pintype "passive"))
      (node (ref "STR_RpudMiso") (pin "2") (pinfunction "2_2") (pintype "passive"))
      (node (ref "STR_RpudMosi") (pin "1") (pinfunction "1_1") (pintype "passive"))
      (node (ref "STR_RpudSck") (pin "2") (pinfunction "2_2") (pintype "passive"))
      (node (ref "STR_RupWAmI") (pin "2") (pinfunction "2_2") (pintype "passive"))
      (node (ref "STR_STM32F4DISCOVERY") (pin "55") (pinfunction "3V_55") (pintype "passive"))
      (node (ref "STR_STM32F4DISCOVERY") (pin "56") (pinfunction "3V_56") (pintype "passive"))
    )
    (net (code "48") (name "5V") (class "Default")
      (node (ref "STR_CdCan1") (pin "2") (pinfunction "2_2") (pintype "passive"))
      (node (ref "STR_CdCan2") (pin "2") (pinfunction "2_2") (pintype "passive"))
      (node (ref "STR_Cd_RTC") (pin "1") (pinfunction "1_1") (pintype "passive"))
      (node (ref "STR_RTC") (pin "8") (pinfunction "VCC_8") (pintype "power_in"))
      (node (ref "STR_Rscl") (pin "2") (pinfunction "2_2") (pintype "passive"))
      (node (ref "STR_Rsda") (pin "2") (pinfunction "2_2") (pintype "passive"))
      (node (ref "STR_STM32F4DISCOVERY") (pin "53") (pinfunction "5V_53") (pintype "passive"))
      (node (ref "STR_STM32F4DISCOVERY") (pin "54") (pinfunction "5V_54") (pintype "passive"))
      (node (ref "STR_Ucan") (pin "3") (pinfunction "VDD_3") (pintype "power_in"))
    )
    (net (code "49") (name "5V_Perm") (class "Default")
      (node (ref "STR_UART1") (pin "1") (pinfunction "1_1") (pintype "passive"))
      (node (ref "STR_UART1") (pin "2") (pinfunction "2_2") (pintype "passive"))
    )
    (net (code "50") (name "24V") (class "Default")
      (node (ref "STR_CdDtb1") (pin "2") (pinfunction "2_2") (pintype "passive"))
      (node (ref "STR_CdDtc1") (pin "2") (pinfunction "2_2") (pintype "passive"))
      (node (ref "STR_CdDtc2") (pin "2") (pinfunction "2_2") (pintype "passive"))
      (node (ref "STR_CdDtc3") (pin "2") (pinfunction "2_2") (pintype "passive"))
      (node (ref "STR_CdDtc4") (pin "2") (pinfunction "2_2") (pintype "passive"))
      (node (ref "STR_DTb1") (pin "3") (pinfunction "3_3") (pintype "passive"))
      (node (ref "STR_DTc1") (pin "3") (pinfunction "3_3") (pintype "passive"))
      (node (ref "STR_DTc2") (pin "3") (pinfunction "3_3") (pintype "passive"))
      (node (ref "STR_DTc3") (pin "3") (pinfunction "3_3") (pintype "passive"))
      (node (ref "STR_DTc4") (pin "3") (pinfunction "3_3") (pintype "passive"))
      (node (ref "STR_mes24+") (pin "2") (pinfunction "2_2") (pintype "passive"))
    )
    (net (code "51") (name "GND") (class "Default")
      (node (ref "STR_Buz") (pin "2") (pinfunction "2_2") (pintype "passive"))
      (node (ref "STR_CR2032") (pin "2") (pinfunction "-_2") (pintype "power_in"))
      (node (ref "STR_Cd1SD") (pin "1") (pinfunction "1_1") (pintype "passive"))
      (node (ref "STR_Cd2SD") (pin "1") (pinfunction "1_1") (pintype "passive"))
      (node (ref "STR_CdCan1") (pin "1") (pinfunction "1_1") (pintype "passive"))
      (node (ref "STR_CdCan2") (pin "1") (pinfunction "1_1") (pintype "passive"))
      (node (ref "STR_Cd_RTC") (pin "2") (pinfunction "2_2") (pintype "passive"))
      (node (ref "STR_CfB4") (pin "1") (pinfunction "1_1") (pintype "passive"))
      (node (ref "STR_CfB5") (pin "1") (pinfunction "1_1") (pintype "passive"))
      (node (ref "STR_CfC5") (pin "1") (pinfunction "1_1") (pintype "passive"))
      (node (ref "STR_CfDTb1") (pin "1") (pinfunction "1_1") (pintype "passive"))
      (node (ref "STR_CfDTc1") (pin "1") (pinfunction "1_1") (pintype "passive"))
      (node (ref "STR_CfDTc2") (pin "1") (pinfunction "1_1") (pintype "passive"))
      (node (ref "STR_CfDTc3") (pin "1") (pinfunction "1_1") (pintype "passive"))
      (node (ref "STR_CfDTc4") (pin "1") (pinfunction "1_1") (pintype "passive"))
      (node (ref "STR_Cmes24") (pin "1") (pinfunction "1_1") (pintype "passive"))
      (node (ref "STR_Cu1rx") (pin "1") (pinfunction "1_1") (pintype "passive"))
      (node (ref "STR_DSelftest") (pin "2") (pinfunction "K_2") (pintype "passive"))
      (node (ref "STR_Dbuz") (pin "3") (pinfunction "A_3") (pintype "passive"))
      (node (ref "STR_Derror") (pin "2") (pinfunction "K_2") (pintype "passive"))
      (node (ref "STR_MICRO_SD") (pin "0") (pinfunction "CAP_0") (pintype "passive"))
      (node (ref "STR_MICRO_SD") (pin "6") (pinfunction "VSS_6") (pintype "passive"))
      (node (ref "STR_MICRO_SD") (pin "9") (pinfunction "Nail_Gnd_9") (pintype "passive"))
      (node (ref "STR_PB4") (pin "1") (pinfunction "1_1") (pintype "passive"))
      (node (ref "STR_PB5") (pin "1") (pinfunction "1_1") (pintype "passive"))
      (node (ref "STR_PC5") (pin "1") (pinfunction "1_1") (pintype "passive"))
      (node (ref "STR_RTC") (pin "4") (pinfunction "GND_4") (pintype "power_in"))
      (node (ref "STR_Rdtb1") (pin "1") (pinfunction "1_1") (pintype "passive"))
      (node (ref "STR_Rdtc1") (pin "1") (pinfunction "1_1") (pintype "passive"))
      (node (ref "STR_Rdtc2") (pin "1") (pinfunction "1_1") (pintype "passive"))
      (node (ref "STR_Rdtc3") (pin "1") (pinfunction "1_1") (pintype "passive"))
      (node (ref "STR_Rdtc4") (pin "1") (pinfunction "1_1") (pintype "passive"))
      (node (ref "STR_RdwnWAmI") (pin "1") (pinfunction "1_1") (pintype "passive"))
      (node (ref "STR_STM32F4DISCOVERY") (pin "1") (pinfunction "GND_1") (pintype "passive"))
      (node (ref "STR_STM32F4DISCOVERY") (pin "100") (pinfunction "GND_100") (pintype "passive"))
      (node (ref "STR_STM32F4DISCOVERY") (pin "2") (pinfunction "GND_2") (pintype "passive"))
      (node (ref "STR_STM32F4DISCOVERY") (pin "23") (pinfunction "GND_23") (pintype "passive"))
      (node (ref "STR_STM32F4DISCOVERY") (pin "49") (pinfunction "GND_49") (pintype "passive"))
      (node (ref "STR_STM32F4DISCOVERY") (pin "5") (pinfunction "GND_5") (pintype "passive"))
      (node (ref "STR_STM32F4DISCOVERY") (pin "50") (pinfunction "GND_50") (pintype "passive"))
      (node (ref "STR_STM32F4DISCOVERY") (pin "51") (pinfunction "GND_51") (pintype "passive"))
      (node (ref "STR_STM32F4DISCOVERY") (pin "52") (pinfunction "GND_52") (pintype "passive"))
      (node (ref "STR_STM32F4DISCOVERY") (pin "99") (pinfunction "GND_99") (pintype "passive"))
      (node (ref "STR_UART1") (pin "5") (pinfunction "5_5") (pintype "passive"))
      (node (ref "STR_UART1") (pin "6") (pinfunction "6_6") (pintype "passive"))
      (node (ref "STR_Ucan") (pin "2") (pinfunction "VSS_2") (pintype "power_in"))
      (node (ref "STR_Ucan") (pin "8") (pinfunction "RS_8") (pintype "input"))
      (node (ref "st_i_am_s") (pin "1") (pinfunction "1_1") (pintype "passive"))
    )
    (net (code "52") (name "GND_24") (class "Default")
      (node (ref "STR_CdDtb1") (pin "1") (pinfunction "1_1") (pintype "passive"))
      (node (ref "STR_CdDtc1") (pin "1") (pinfunction "1_1") (pintype "passive"))
      (node (ref "STR_CdDtc2") (pin "1") (pinfunction "1_1") (pintype "passive"))
      (node (ref "STR_CdDtc3") (pin "1") (pinfunction "1_1") (pintype "passive"))
      (node (ref "STR_CdDtc4") (pin "1") (pinfunction "1_1") (pintype "passive"))
      (node (ref "STR_DTb1") (pin "1") (pinfunction "1_1") (pintype "passive"))
      (node (ref "STR_DTc1") (pin "1") (pinfunction "1_1") (pintype "passive"))
      (node (ref "STR_DTc2") (pin "1") (pinfunction "1_1") (pintype "passive"))
      (node (ref "STR_DTc3") (pin "1") (pinfunction "1_1") (pintype "passive"))
      (node (ref "STR_DTc4") (pin "1") (pinfunction "1_1") (pintype "passive"))
      (node (ref "STR_mes24-") (pin "1") (pinfunction "1_1") (pintype "passive"))
    )
    (net (code "53") (name "Net-(STR_CR2032-+)") (class "Default")
      (node (ref "STR_CR2032") (pin "1") (pinfunction "+_1") (pintype "power_in"))
      (node (ref "STR_RTC") (pin "3") (pinfunction "VBAT_3") (pintype "power_in"))
    )
    (net (code "54") (name "Net-(STR_DSelftest-A)") (class "Default")
      (node (ref "STR_DSelftest") (pin "1") (pinfunction "A_1") (pintype "passive"))
      (node (ref "STR_Rdselftest") (pin "2") (pinfunction "2_2") (pintype "passive"))
    )
    (net (code "55") (name "Net-(STR_DTb1-Pad2)") (class "Default")
      (node (ref "STR_DTb1") (pin "2") (pinfunction "2_2") (pintype "passive"))
      (node (ref "STR_Rdtb1") (pin "2") (pinfunction "2_2") (pintype "passive"))
      (node (ref "STR_RfDTb1") (pin "1") (pinfunction "1_1") (pintype "passive"))
    )
    (net (code "56") (name "Net-(STR_DTc1-Pad2)") (class "Default")
      (node (ref "STR_DTc1") (pin "2") (pinfunction "2_2") (pintype "passive"))
      (node (ref "STR_Rdtc1") (pin "2") (pinfunction "2_2") (pintype "passive"))
      (node (ref "STR_RfDTc1") (pin "1") (pinfunction "1_1") (pintype "passive"))
    )
    (net (code "57") (name "Net-(STR_DTc2-Pad2)") (class "Default")
      (node (ref "STR_DTc2") (pin "2") (pinfunction "2_2") (pintype "passive"))
      (node (ref "STR_Rdtc2") (pin "2") (pinfunction "2_2") (pintype "passive"))
      (node (ref "STR_RfDTc2") (pin "1") (pinfunction "1_1") (pintype "passive"))
    )
    (net (code "58") (name "Net-(STR_DTc3-Pad2)") (class "Default")
      (node (ref "STR_DTc3") (pin "2") (pinfunction "2_2") (pintype "passive"))
      (node (ref "STR_Rdtc3") (pin "2") (pinfunction "2_2") (pintype "passive"))
      (node (ref "STR_RfDTc3") (pin "1") (pinfunction "1_1") (pintype "passive"))
    )
    (net (code "59") (name "Net-(STR_DTc4-Pad2)") (class "Default")
      (node (ref "STR_DTc4") (pin "2") (pinfunction "2_2") (pintype "passive"))
      (node (ref "STR_Rdtc4") (pin "2") (pinfunction "2_2") (pintype "passive"))
      (node (ref "STR_RfDTc4") (pin "1") (pinfunction "1_1") (pintype "passive"))
    )
    (net (code "60") (name "Net-(STR_Dbuz-K1)") (class "Default")
      (node (ref "STR_Buz") (pin "1") (pinfunction "1_1") (pintype "passive"))
      (node (ref "STR_Dbuz") (pin "1") (pinfunction "K1_1") (pintype "passive"))
      (node (ref "STR_Rvarbuz") (pin "3") (pinfunction "3_3") (pintype "passive"))
    )
    (net (code "61") (name "Net-(STR_Derror-A)") (class "Default")
      (node (ref "STR_Derror") (pin "1") (pinfunction "A_1") (pintype "passive"))
      (node (ref "STR_Rderror") (pin "2") (pinfunction "2_2") (pintype "passive"))
    )
    (net (code "62") (name "Net-(STR_MICRO_SD-CS)") (class "Default")
      (node (ref "STR_MICRO_SD") (pin "2") (pinfunction "CS_2") (pintype "passive"))
      (node (ref "STR_RsdCS") (pin "2") (pinfunction "2_2") (pintype "passive"))
    )
    (net (code "63") (name "Net-(STR_MICRO_SD-DI)") (class "Default")
      (node (ref "STR_MICRO_SD") (pin "3") (pinfunction "DI_3") (pintype "passive"))
      (node (ref "STR_RsdMosi") (pin "2") (pinfunction "2_2") (pintype "passive"))
    )
    (net (code "64") (name "Net-(STR_MICRO_SD-DO)") (class "Default")
      (node (ref "STR_MICRO_SD") (pin "7") (pinfunction "DO_7") (pintype "passive"))
      (node (ref "STR_RsdMiso") (pin "2") (pinfunction "2_2") (pintype "passive"))
    )
    (net (code "65") (name "Net-(STR_MICRO_SD-SCLK)") (class "Default")
      (node (ref "STR_MICRO_SD") (pin "5") (pinfunction "SCLK_5") (pintype "passive"))
      (node (ref "STR_RsdSck") (pin "2") (pinfunction "2_2") (pintype "passive"))
    )
    (net (code "66") (name "Net-(STR_PB4-Pad2)") (class "Default")
      (node (ref "STR_PB4") (pin "2") (pinfunction "2_2") (pintype "passive"))
      (node (ref "STR_RfB4") (pin "1") (pinfunction "1_1") (pintype "passive"))
    )
    (net (code "67") (name "Net-(STR_PB5-Pad2)") (class "Default")
      (node (ref "STR_PB5") (pin "2") (pinfunction "2_2") (pintype "passive"))
      (node (ref "STR_RfB5") (pin "1") (pinfunction "1_1") (pintype "passive"))
    )
    (net (code "68") (name "Net-(STR_PC5-Pad2)") (class "Default")
      (node (ref "STR_PC5") (pin "2") (pinfunction "2_2") (pintype "passive"))
      (node (ref "STR_RfC5") (pin "1") (pinfunction "1_1") (pintype "passive"))
    )
    (net (code "69") (name "Net-(STR_RTC-X1)") (class "Default")
      (node (ref "STR_Qz") (pin "1") (pinfunction "1_1") (pintype "passive"))
      (node (ref "STR_RTC") (pin "1") (pinfunction "X1_1") (pintype "input"))
    )
    (net (code "70") (name "Net-(STR_RTC-X2)") (class "Default")
      (node (ref "STR_Qz") (pin "4") (pinfunction "4_4") (pintype "passive"))
      (node (ref "STR_RTC") (pin "2") (pinfunction "X2_2") (pintype "input"))
    )
    (net (code "71") (name "Net-(STR_RsBuz-Pad2)") (class "Default")
      (node (ref "STR_RsBuz") (pin "2") (pinfunction "2_2") (pintype "passive"))
      (node (ref "STR_Rvarbuz") (pin "2") (pinfunction "2_2") (pintype "passive"))
    )
    (net (code "72") (name "Net-(STR_Rsmed24-Pad1)") (class "Default")
      (node (ref "STR_Rsmed24") (pin "1") (pinfunction "1_1") (pintype "passive"))
      (node (ref "STR_mes24+") (pin "1") (pinfunction "1_1") (pintype "passive"))
      (node (ref "STR_mes24-") (pin "2") (pinfunction "2_2") (pintype "passive"))
    )
    (net (code "73") (name "unconnected-(STR_Dbuz-K2-Pad2)") (class "Default")
      (node (ref "STR_Dbuz") (pin "2") (pinfunction "K2_2") (pintype "passive+no_connect"))
    )
    (net (code "74") (name "unconnected-(STR_MICRO_SD-Nail-Pad10)") (class "Default")
      (node (ref "STR_MICRO_SD") (pin "10") (pinfunction "Nail_10") (pintype "passive"))
    )
    (net (code "75") (name "unconnected-(STR_MICRO_SD-X-Pad1)") (class "Default")
      (node (ref "STR_MICRO_SD") (pin "1") (pinfunction "X_1") (pintype "passive+no_connect"))
    )
    (net (code "76") (name "unconnected-(STR_MICRO_SD-X-Pad8)") (class "Default")
      (node (ref "STR_MICRO_SD") (pin "8") (pinfunction "X_8") (pintype "passive+no_connect"))
    )
    (net (code "77") (name "unconnected-(STR_Qz-Pad2)") (class "Default")
      (node (ref "STR_Qz") (pin "2") (pinfunction "2_2") (pintype "passive"))
    )
    (net (code "78") (name "unconnected-(STR_Qz-Pad3)") (class "Default")
      (node (ref "STR_Qz") (pin "3") (pinfunction "3_3") (pintype "passive"))
    )
    (net (code "79") (name "unconnected-(STR_RTC-SQW{slash}OUT-Pad7)") (class "Default")
      (node (ref "STR_RTC") (pin "7") (pinfunction "SQW/OUT_7") (pintype "output+no_connect"))
    )
    (net (code "80") (name "unconnected-(STR_Rvarbuz-Pad1)") (class "Default")
      (node (ref "STR_Rvarbuz") (pin "1") (pinfunction "1_1") (pintype "passive+no_connect"))
    )
    (net (code "81") (name "unconnected-(STR_STM32F4DISCOVERY-BOOT0{slash}VPP-Pad71)") (class "Default")
      (node (ref "STR_STM32F4DISCOVERY") (pin "71") (pinfunction "BOOT0/VPP_71") (pintype "passive+no_connect"))
    )
    (net (code "82") (name "unconnected-(STR_STM32F4DISCOVERY-NC-Pad48)") (class "Default")
      (node (ref "STR_STM32F4DISCOVERY") (pin "48") (pinfunction "NC_48") (pintype "passive+no_connect"))
    )
    (net (code "83") (name "unconnected-(STR_STM32F4DISCOVERY-NRST-Pad6)") (class "Default")
      (node (ref "STR_STM32F4DISCOVERY") (pin "6") (pinfunction "NRST_6") (pintype "passive+no_connect"))
    )
    (net (code "84") (name "unconnected-(STR_STM32F4DISCOVERY-PA1{slash}USART2_RTS{slash}USART4_RX{slash}ETH_RMII_REF_CLK{slash}ETH_MII_RX_CLK{slash}TIM5_CH2{slash}TIMM2_CH2{slash}ADC123_IN1-Pad11)") (class "Default")
      (node (ref "STR_STM32F4DISCOVERY") (pin "11") (pinfunction "PA1/USART2_RTS/USART4_RX/ETH_RMII_REF_CLK/ETH_MII_RX_CLK/TIM5_CH2/TIMM2_CH2/ADC123_IN1_11") (pintype "passive"))
    )
    (net (code "85") (name "unconnected-(STR_STM32F4DISCOVERY-PA4{slash}SPI1_NSS{slash}SPI3_NSS{slash}USART2_CK{slash}DCMI_HSYNC{slash}OTG_HS_SOF{slash}I2S3_WS{slash}ADC12_IN4{slash}DAC1_OUT-Pad16)") (class "Default")
      (node (ref "STR_STM32F4DISCOVERY") (pin "16") (pinfunction "PA4/SPI1_NSS/SPI3_NSS/USART2_CK/DCMI_HSYNC/OTG_HS_SOF/I2S3_WS/ADC12_IN4/DAC1_OUT_16") (pintype "passive+no_connect"))
    )
    (net (code "86") (name "unconnected-(STR_STM32F4DISCOVERY-PA7{slash}SPI1_MOSI{slash}TIM8_CH1N{slash}TIM14_CH1TIM3_CH2{slash}ETH_MII_RX_DV{slash}TIM1_CH1N{slash}RMII_CRS_DV{slash}ADC12_IN7-Pad17)") (class "Default")
      (node (ref "STR_STM32F4DISCOVERY") (pin "17") (pinfunction "PA7/SPI1_MOSI/TIM8_CH1N/TIM14_CH1TIM3_CH2/ETH_MII_RX_DV/TIM1_CH1N/RMII_CRS_DV/ADC12_IN7_17") (pintype "passive"))
    )
    (net (code "87") (name "unconnected-(STR_STM32F4DISCOVERY-PA8{slash}MCO1{slash}USART1_CK{slash}TIM1_CH1{slash}I2C3_SCL{slash}OTG_FS_SOF-Pad93)") (class "Default")
      (node (ref "STR_STM32F4DISCOVERY") (pin "93") (pinfunction "PA8/MCO1/USART1_CK/TIM1_CH1/I2C3_SCL/OTG_FS_SOF_93") (pintype "passive"))
    )
    (net (code "88") (name "unconnected-(STR_STM32F4DISCOVERY-PA9{slash}USART1_TX{slash}TIM1_CH2{slash}I2C3_SMBA{slash}DCMI_D0{slash}OTG_FS_VBUS-Pad94)") (class "Default")
      (node (ref "STR_STM32F4DISCOVERY") (pin "94") (pinfunction "PA9/USART1_TX/TIM1_CH2/I2C3_SMBA/DCMI_D0/OTG_FS_VBUS_94") (pintype "passive+no_connect"))
    )
    (net (code "89") (name "unconnected-(STR_STM32F4DISCOVERY-PA10{slash}USART1_RX{slash}TIM1_CH3{slash}OTG_FS_ID{slash}DCMI_D1-Pad91)") (class "Default")
      (node (ref "STR_STM32F4DISCOVERY") (pin "91") (pinfunction "PA10/USART1_RX/TIM1_CH3/OTG_FS_ID/DCMI_D1_91") (pintype "passive+no_connect"))
    )
    (net (code "90") (name "unconnected-(STR_STM32F4DISCOVERY-PA13{slash}JTMS_SWDIO-Pad92)") (class "Default")
      (node (ref "STR_STM32F4DISCOVERY") (pin "92") (pinfunction "PA13/JTMS_SWDIO_92") (pintype "passive+no_connect"))
    )
    (net (code "91") (name "unconnected-(STR_STM32F4DISCOVERY-PA14{slash}JTCK_SWCLK-Pad89)") (class "Default")
      (node (ref "STR_STM32F4DISCOVERY") (pin "89") (pinfunction "PA14/JTCK_SWCLK_89") (pintype "passive+no_connect"))
    )
    (net (code "92") (name "unconnected-(STR_STM32F4DISCOVERY-PA15{slash}JTDI{slash}SPI3_NSS{slash}I2S3_WS{slash}TIM2_CH1_ETR{slash}SPI1_NSS-Pad90)") (class "Default")
      (node (ref "STR_STM32F4DISCOVERY") (pin "90") (pinfunction "PA15/JTDI/SPI3_NSS/I2S3_WS/TIM2_CH1_ETR/SPI1_NSS_90") (pintype "passive"))
    )
    (net (code "93") (name "unconnected-(STR_STM32F4DISCOVERY-PB3{slash}JTDO{slash}TRACESWO{slash}SPI3_SCK{slash}I2S3_CK{slash}TIM2_CH2{slash}SPI1_SCK-Pad78)") (class "Default")
      (node (ref "STR_STM32F4DISCOVERY") (pin "78") (pinfunction "PB3/JTDO/TRACESWO/SPI3_SCK/I2S3_CK/TIM2_CH2/SPI1_SCK_78") (pintype "passive+no_connect"))
    )
    (net (code "94") (name "unconnected-(STR_STM32F4DISCOVERY-PB8{slash}TIM4_CH3{slash}SDIO_D4{slash}TIM10_CH1{slash}DCMI_D6{slash}OTG_FS_SCL{slash}ETH_MII_TXD3{slash}I2C1_SCL{slash}CAN1_RX-Pad69)") (class "Default")
      (node (ref "STR_STM32F4DISCOVERY") (pin "69") (pinfunction "PB8/TIM4_CH3/SDIO_D4/TIM10_CH1/DCMI_D6/OTG_FS_SCL/ETH_MII_TXD3/I2C1_SCL/CAN1_RX_69") (pintype "passive+no_connect"))
    )
    (net (code "95") (name "unconnected-(STR_STM32F4DISCOVERY-PC0{slash}OTG_HS_ULPI_STP{slash}ADC123_IN10-Pad8)") (class "Default")
      (node (ref "STR_STM32F4DISCOVERY") (pin "8") (pinfunction "PC0/OTG_HS_ULPI_STP/ADC123_IN10_8") (pintype "passive+no_connect"))
    )
    (net (code "96") (name "unconnected-(STR_STM32F4DISCOVERY-PC6{slash}I2S2_MCK{slash}TIM8_CH1{slash}SDIO_D6{slash}USART6_TX{slash}DCMI_D0{slash}TIM3_CH1-Pad97)") (class "Default")
      (node (ref "STR_STM32F4DISCOVERY") (pin "97") (pinfunction "PC6/I2S2_MCK/TIM8_CH1/SDIO_D6/USART6_TX/DCMI_D0/TIM3_CH1_97") (pintype "passive"))
    )
    (net (code "97") (name "unconnected-(STR_STM32F4DISCOVERY-PC7{slash}I2S3_MCK{slash}TIM8_CH2{slash}SDIO_D7{slash}USART6_RX_DCMI_D1{slash}TIM3_CH2-Pad98)") (class "Default")
      (node (ref "STR_STM32F4DISCOVERY") (pin "98") (pinfunction "PC7/I2S3_MCK/TIM8_CH2/SDIO_D7/USART6_RX_DCMI_D1/TIM3_CH2_98") (pintype "passive"))
    )
    (net (code "98") (name "unconnected-(STR_STM32F4DISCOVERY-PC10{slash}SPI3_SCK{slash}I2S3_CK{slash}UART4_TX{slash}SDIO_D2{slash}DCMI_D8{slash}USART3_TX-Pad87)") (class "Default")
      (node (ref "STR_STM32F4DISCOVERY") (pin "87") (pinfunction "PC10/SPI3_SCK/I2S3_CK/UART4_TX/SDIO_D2/DCMI_D8/USART3_TX_87") (pintype "passive"))
    )
    (net (code "99") (name "unconnected-(STR_STM32F4DISCOVERY-PC11{slash}UART4_RX{slash}SPI3_MISO{slash}SDIO_D3{slash}DCMI_D4{slash}USART3_RX{slash}I2S3ext_SD-Pad88)") (class "Default")
      (node (ref "STR_STM32F4DISCOVERY") (pin "88") (pinfunction "PC11/UART4_RX/SPI3_MISO/SDIO_D3/DCMI_D4/USART3_RX/I2S3ext_SD_88") (pintype "passive"))
    )
    (net (code "100") (name "unconnected-(STR_STM32F4DISCOVERY-PC12{slash}UART5_TX{slash}SDIO_CK{slash}DCMI_D9{slash}SPI3_MOSI{slash}I2S3_SD{slash}USART3_CK-Pad85)") (class "Default")
      (node (ref "STR_STM32F4DISCOVERY") (pin "85") (pinfunction "PC12/UART5_TX/SDIO_CK/DCMI_D9/SPI3_MOSI/I2S3_SD/USART3_CK_85") (pintype "passive"))
    )
    (net (code "101") (name "unconnected-(STR_STM32F4DISCOVERY-PC14{slash}OSC32_IN-Pad59)") (class "Default")
      (node (ref "STR_STM32F4DISCOVERY") (pin "59") (pinfunction "PC14/OSC32_IN_59") (pintype "passive+no_connect"))
    )
    (net (code "102") (name "unconnected-(STR_STM32F4DISCOVERY-PC15{slash}OSC32_OUT-Pad60)") (class "Default")
      (node (ref "STR_STM32F4DISCOVERY") (pin "60") (pinfunction "PC15/OSC32_OUT_60") (pintype "passive+no_connect"))
    )
    (net (code "103") (name "unconnected-(STR_STM32F4DISCOVERY-PD2{slash}TIM3_ETR{slash}UART5_RXSDIO_CMD{slash}DCMI_D11-Pad84)") (class "Default")
      (node (ref "STR_STM32F4DISCOVERY") (pin "84") (pinfunction "PD2/TIM3_ETR/UART5_RXSDIO_CMD/DCMI_D11_84") (pintype "passive"))
    )
    (net (code "104") (name "unconnected-(STR_STM32F4DISCOVERY-PD3{slash}FSMC_CLK{slash}USART2_CTS-Pad81)") (class "Default")
      (node (ref "STR_STM32F4DISCOVERY") (pin "81") (pinfunction "PD3/FSMC_CLK/USART2_CTS_81") (pintype "passive"))
    )
    (net (code "105") (name "unconnected-(STR_STM32F4DISCOVERY-PD4{slash}FSMC_NOE{slash}USART2_RTS-Pad82)") (class "Default")
      (node (ref "STR_STM32F4DISCOVERY") (pin "82") (pinfunction "PD4/FSMC_NOE/USART2_RTS_82") (pintype "passive"))
    )
    (net (code "106") (name "unconnected-(STR_STM32F4DISCOVERY-PD5{slash}FSMC_NWE{slash}USART2_TX-Pad79)") (class "Default")
      (node (ref "STR_STM32F4DISCOVERY") (pin "79") (pinfunction "PD5/FSMC_NWE/USART2_TX_79") (pintype "passive+no_connect"))
    )
    (net (code "107") (name "unconnected-(STR_STM32F4DISCOVERY-PD6{slash}FSMC_NWAIT{slash}USART2_RX-Pad80)") (class "Default")
      (node (ref "STR_STM32F4DISCOVERY") (pin "80") (pinfunction "PD6/FSMC_NWAIT/USART2_RX_80") (pintype "passive"))
    )
    (net (code "108") (name "unconnected-(STR_STM32F4DISCOVERY-PD7{slash}USART2_CK{slash}FSMC_NE1{slash}FSMC_NCE2-Pad77)") (class "Default")
      (node (ref "STR_STM32F4DISCOVERY") (pin "77") (pinfunction "PD7/USART2_CK/FSMC_NE1/FSMC_NCE2_77") (pintype "passive"))
    )
    (net (code "109") (name "unconnected-(STR_STM32F4DISCOVERY-PE0{slash}TIM4_ETR{slash}FSMC_NBL0{slash}DCMI_D2-Pad67)") (class "Default")
      (node (ref "STR_STM32F4DISCOVERY") (pin "67") (pinfunction "PE0/TIM4_ETR/FSMC_NBL0/DCMI_D2_67") (pintype "passive+no_connect"))
    )
    (net (code "110") (name "unconnected-(STR_STM32F4DISCOVERY-PE1{slash}FSMC_NBL1{slash}DCMI_D3-Pad68)") (class "Default")
      (node (ref "STR_STM32F4DISCOVERY") (pin "68") (pinfunction "PE1/FSMC_NBL1/DCMI_D3_68") (pintype "passive+no_connect"))
    )
    (net (code "111") (name "unconnected-(STR_STM32F4DISCOVERY-PE2{slash}TRACECLK{slash}FSMC_A23{slash}ETH_MII_TXD3-Pad65)") (class "Default")
      (node (ref "STR_STM32F4DISCOVERY") (pin "65") (pinfunction "PE2/TRACECLK/FSMC_A23/ETH_MII_TXD3_65") (pintype "passive+no_connect"))
    )
    (net (code "112") (name "unconnected-(STR_STM32F4DISCOVERY-PE3{slash}TRACED0{slash}FSMC_A19-Pad66)") (class "Default")
      (node (ref "STR_STM32F4DISCOVERY") (pin "66") (pinfunction "PE3/TRACED0/FSMC_A19_66") (pintype "passive+no_connect"))
    )
    (net (code "113") (name "unconnected-(STR_STM32F4DISCOVERY-PE4{slash}TRACED1{slash}FSMC_A20{slash}DCMI_D4-Pad63)") (class "Default")
      (node (ref "STR_STM32F4DISCOVERY") (pin "63") (pinfunction "PE4/TRACED1/FSMC_A20/DCMI_D4_63") (pintype "passive+no_connect"))
    )
    (net (code "114") (name "unconnected-(STR_STM32F4DISCOVERY-PE5{slash}TRACED2{slash}FSMC_A21{slash}TIM9_CH1{slash}DCMI_D6-Pad64)") (class "Default")
      (node (ref "STR_STM32F4DISCOVERY") (pin "64") (pinfunction "PE5/TRACED2/FSMC_A21/TIM9_CH1/DCMI_D6_64") (pintype "passive+no_connect"))
    )
    (net (code "115") (name "unconnected-(STR_STM32F4DISCOVERY-PE6{slash}TRACED3{slash}FSMC_A22{slash}TIM9_CH2{slash}DCMI_D7-Pad61)") (class "Default")
      (node (ref "STR_STM32F4DISCOVERY") (pin "61") (pinfunction "PE6/TRACED3/FSMC_A22/TIM9_CH2/DCMI_D7_61") (pintype "passive+no_connect"))
    )
    (net (code "116") (name "unconnected-(STR_STM32F4DISCOVERY-PE11{slash}FSMC_D8{slash}TIM1_CH2-Pad29)") (class "Default")
      (node (ref "STR_STM32F4DISCOVERY") (pin "29") (pinfunction "PE11/FSMC_D8/TIM1_CH2_29") (pintype "passive"))
    )
    (net (code "117") (name "unconnected-(STR_STM32F4DISCOVERY-PE12{slash}FSMC_D9{slash}TIM1_CH3N-Pad30)") (class "Default")
      (node (ref "STR_STM32F4DISCOVERY") (pin "30") (pinfunction "PE12/FSMC_D9/TIM1_CH3N_30") (pintype "passive"))
    )
    (net (code "118") (name "unconnected-(STR_STM32F4DISCOVERY-PE13{slash}FSMC_D10{slash}TIM1_CH3-Pad31)") (class "Default")
      (node (ref "STR_STM32F4DISCOVERY") (pin "31") (pinfunction "PE13/FSMC_D10/TIM1_CH3_31") (pintype "passive"))
    )
    (net (code "119") (name "unconnected-(STR_STM32F4DISCOVERY-PE14{slash}FSMC_D11{slash}TIM1_CH4-Pad32)") (class "Default")
      (node (ref "STR_STM32F4DISCOVERY") (pin "32") (pinfunction "PE14/FSMC_D11/TIM1_CH4_32") (pintype "passive"))
    )
    (net (code "120") (name "unconnected-(STR_STM32F4DISCOVERY-PE15{slash}FSMC_D12{slash}TIM1_BKIN-Pad33)") (class "Default")
      (node (ref "STR_STM32F4DISCOVERY") (pin "33") (pinfunction "PE15/FSMC_D12/TIM1_BKIN_33") (pintype "passive"))
    )
    (net (code "121") (name "unconnected-(STR_STM32F4DISCOVERY-PH0{slash}OSC_IN-Pad57)") (class "Default")
      (node (ref "STR_STM32F4DISCOVERY") (pin "57") (pinfunction "PH0/OSC_IN_57") (pintype "passive+no_connect"))
    )
    (net (code "122") (name "unconnected-(STR_STM32F4DISCOVERY-PH1{slash}OSC_OUT-Pad58)") (class "Default")
      (node (ref "STR_STM32F4DISCOVERY") (pin "58") (pinfunction "PH1/OSC_OUT_58") (pintype "passive+no_connect"))
    )
    (net (code "123") (name "unconnected-(STR_STM32F4DISCOVERY-VDD-Pad3)") (class "Default")
      (node (ref "STR_STM32F4DISCOVERY") (pin "3") (pinfunction "VDD_3") (pintype "passive+no_connect"))
    )
    (net (code "124") (name "unconnected-(STR_STM32F4DISCOVERY-VDD-Pad4)") (class "Default")
      (node (ref "STR_STM32F4DISCOVERY") (pin "4") (pinfunction "VDD_4") (pintype "passive+no_connect"))
    )
    (net (code "125") (name "unconnected-(STR_STM32F4DISCOVERY-VDD-Pad72)") (class "Default")
      (node (ref "STR_STM32F4DISCOVERY") (pin "72") (pinfunction "VDD_72") (pintype "passive+no_connect"))
    )
    (net (code "126") (name "unconnected-(STR_Ucan-VREF-Pad5)") (class "Default")
      (node (ref "STR_Ucan") (pin "5") (pinfunction "VREF_5") (pintype "output"))
    )
  )
)
